# Pro_Micro.net
KiCad netlist of a schematic drawn in EAGLE
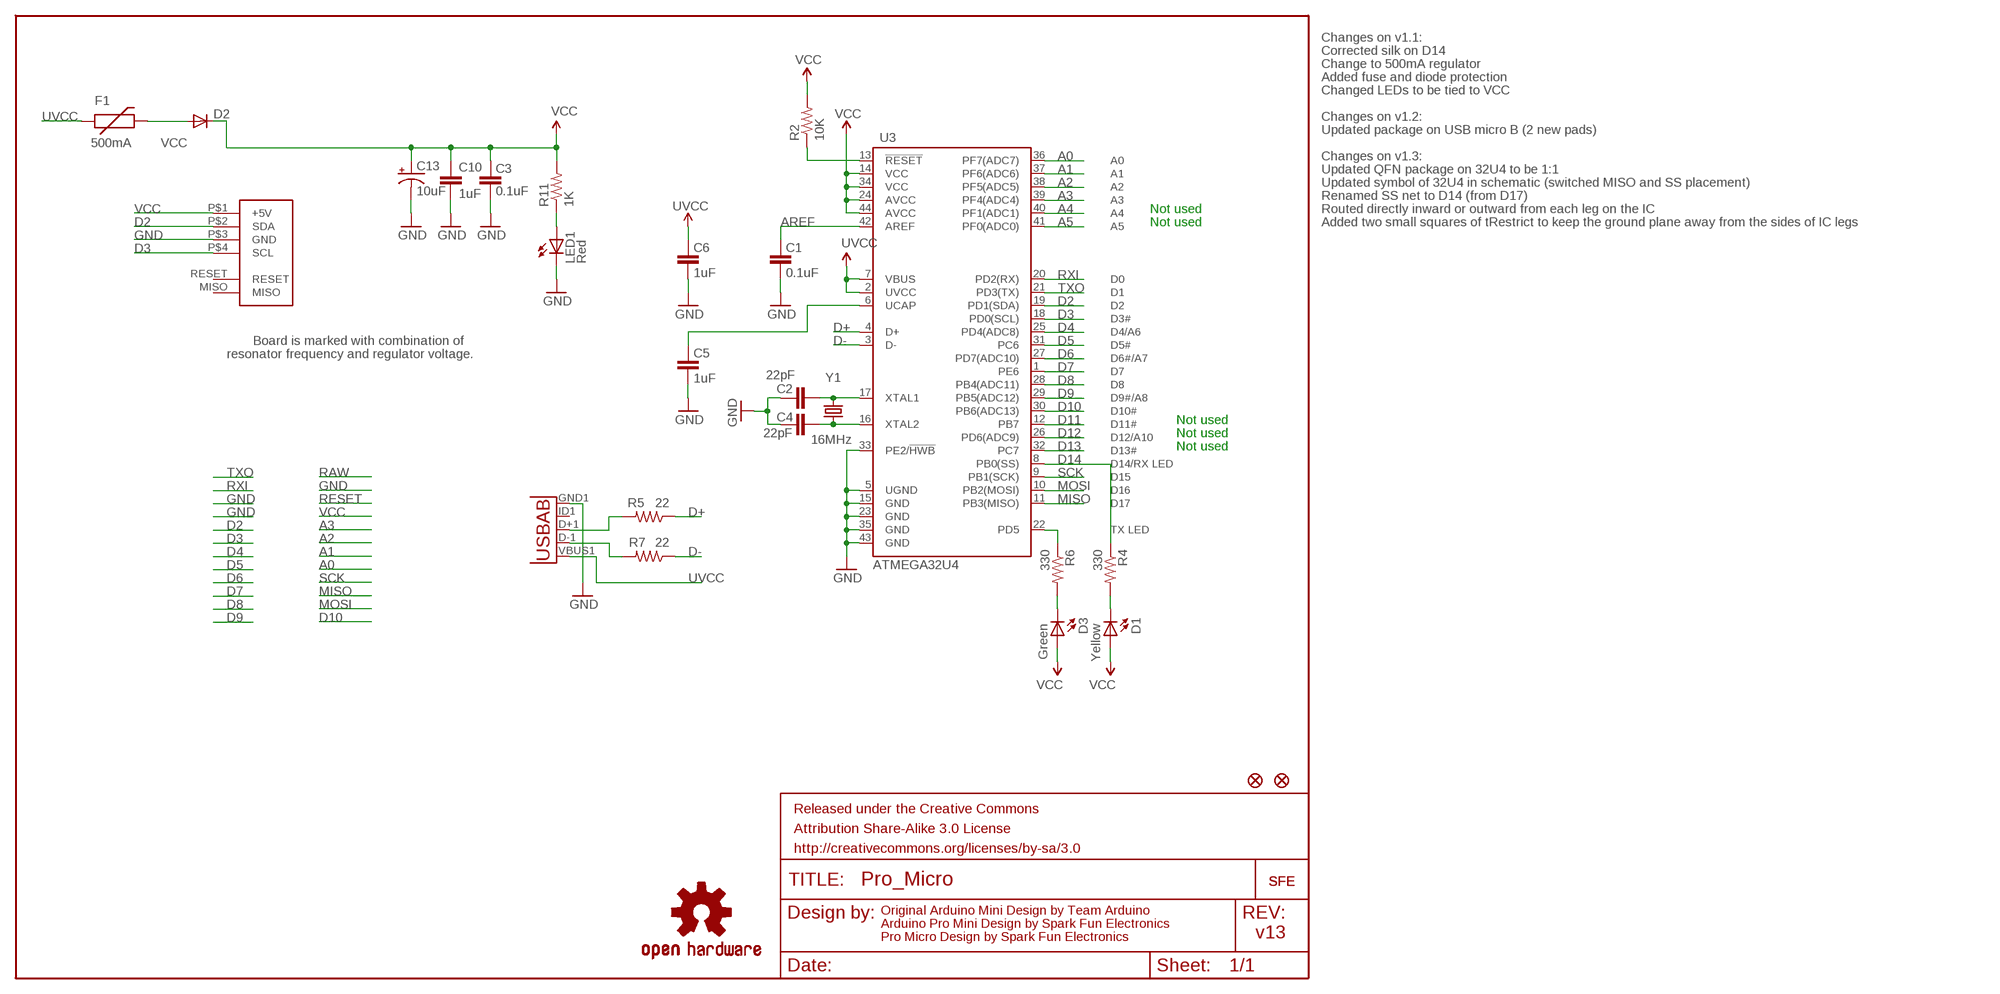
[diagram p0: schematic, sheet 1]

(export (version "E")
  (design (tool "Eeschema 10.0.6"))
  (components
    (comp (ref "C1")
      (value "0.1uF")
      (footprint "eagle-import:0603-CAP")
      (libsource (lib "eagle-import") (part "CAP0603-CAP"))
    )
    (comp (ref "C2")
      (value "22pF")
      (footprint "eagle-import:0603-CAP")
      (libsource (lib "eagle-import") (part "CAP0603-CAP"))
    )
    (comp (ref "C3")
      (value "0.1uF")
      (footprint "eagle-import:0603-CAP")
      (libsource (lib "eagle-import") (part "CAP0603-CAP"))
    )
    (comp (ref "C4")
      (value "22pF")
      (footprint "eagle-import:0603-CAP")
      (libsource (lib "eagle-import") (part "CAP0603-CAP"))
    )
    (comp (ref "C5")
      (value "1uF")
      (footprint "eagle-import:0603-CAP")
      (libsource (lib "eagle-import") (part "CAP0603-CAP"))
    )
    (comp (ref "C6")
      (value "1uF")
      (footprint "eagle-import:0603-CAP")
      (libsource (lib "eagle-import") (part "CAP0603-CAP"))
    )
    (comp (ref "C10")
      (value "1uF")
      (footprint "eagle-import:0603-CAP")
      (libsource (lib "eagle-import") (part "CAP0603-CAP"))
    )
    (comp (ref "C13")
      (value "10uF")
      (footprint "eagle-import:EIA3216")
      (libsource (lib "eagle-import") (part "CAP_POL1206"))
    )
    (comp (ref "D1")
      (value "Yellow")
      (footprint "eagle-import:LED-0603")
      (libsource (lib "eagle-import") (part "LED0603"))
    )
    (comp (ref "D2")
      (value "DIODESOD")
      (footprint "eagle-import:SOD-323")
      (libsource (lib "eagle-import") (part "DIODESOD"))
    )
    (comp (ref "D3")
      (value "Green")
      (footprint "eagle-import:LED-0603")
      (libsource (lib "eagle-import") (part "LED0603"))
    )
    (comp (ref "F1")
      (value "500mA")
      (footprint "eagle-import:PTC-1206")
      (libsource (lib "eagle-import") (part "PTCSMD"))
    )
    (comp (ref "FRAME1")
      (value "FRAME-LETTER")
      (footprint "eagle-import:CREATIVE_COMMONS")
      (libsource (lib "eagle-import") (part "FRAME-LETTER"))
    )
    (comp (ref "JP1")
      (value "FIDUCIALUFIDUCIAL")
      (footprint "eagle-import:MICRO-FIDUCIAL")
      (libsource (lib "eagle-import") (part "FIDUCIALUFIDUCIAL"))
    )
    (comp (ref "JP2")
      (value "FIDUCIALUFIDUCIAL")
      (footprint "eagle-import:MICRO-FIDUCIAL")
      (libsource (lib "eagle-import") (part "FIDUCIALUFIDUCIAL"))
    )
    (comp (ref "LED1")
      (value "Red")
      (footprint "eagle-import:LED-0603")
      (libsource (lib "eagle-import") (part "LED0603"))
    )
    (comp (ref "R2")
      (value "10K")
      (footprint "eagle-import:0603-RES")
      (libsource (lib "eagle-import") (part "RESISTOR0603-RES"))
    )
    (comp (ref "R4")
      (value "330")
      (footprint "eagle-import:0603-RES")
      (libsource (lib "eagle-import") (part "RESISTOR0603-RES"))
    )
    (comp (ref "R5")
      (value "22")
      (footprint "eagle-import:0603-RES")
      (libsource (lib "eagle-import") (part "RESISTOR0603-RES"))
    )
    (comp (ref "R6")
      (value "330")
      (footprint "eagle-import:0603-RES")
      (libsource (lib "eagle-import") (part "RESISTOR0603-RES"))
    )
    (comp (ref "R7")
      (value "22")
      (footprint "eagle-import:0603-RES")
      (libsource (lib "eagle-import") (part "RESISTOR0603-RES"))
    )
    (comp (ref "R11")
      (value "1K")
      (footprint "eagle-import:0603-RES")
      (libsource (lib "eagle-import") (part "RESISTOR0603-RES"))
    )
    (comp (ref "U$1")
      (value "LOGO-SFESK")
      (footprint "eagle-import:SFE-LOGO-FLAME")
      (libsource (lib "eagle-import") (part "LOGO-SFESK"))
    )
    (comp (ref "U$2")
      (value "FOOTPRINT")
      (footprint "eagle-import:FOOTPRINT")
      (libsource (lib "eagle-import") (part "FOOTPRINT"))
    )
    (comp (ref "U$3")
      (value "OSHW-LOGOS")
      (footprint "eagle-import:OSHW-LOGO-S")
      (libsource (lib "eagle-import") (part "OSHW-LOGOS"))
    )
    (comp (ref "U$11")
      (value "LOGO-SFENEW")
      (footprint "eagle-import:SFE-NEW-WEBLOGO")
      (libsource (lib "eagle-import") (part "LOGO-SFENEW"))
    )
    (comp (ref "U3")
      (value "ATMEGA32U4")
      (footprint "eagle-import:QFN-44-NOPAD_1_1-OUTFAKES")
      (libsource (lib "eagle-import") (part "ATMEGA32U4OUTFAKES"))
    )
    (comp (ref "X1")
      (value "USB-ABIN&OUT")
      (footprint "eagle-import:USB-AB-MICRO-SMD-V03-IN&OUT")
      (libsource (lib "eagle-import") (part "USB-ABIN&OUT"))
    )
    (comp (ref "Y1")
      (value "16MHz")
      (footprint "eagle-import:CRYSTAL-SMD-5X3")
      (libsource (lib "eagle-import") (part "CRYSTAL5X3"))
    )
  )
  (nets
    (net (code "1") (name "/A0") (class "Default")
      (node (ref "U3") (pin "36") (pinfunction "PF7(ADC7)_36") (pintype "bidirectional"))
    )
    (net (code "2") (name "/A1") (class "Default")
      (node (ref "U3") (pin "37") (pinfunction "PF6(ADC6)_37") (pintype "bidirectional"))
    )
    (net (code "3") (name "/A2") (class "Default")
      (node (ref "U3") (pin "38") (pinfunction "PF5(ADC5)_38") (pintype "bidirectional"))
    )
    (net (code "4") (name "/A3") (class "Default")
      (node (ref "U3") (pin "39") (pinfunction "PF4(ADC4)_39") (pintype "bidirectional"))
    )
    (net (code "5") (name "/A4") (class "Default")
      (node (ref "U3") (pin "40") (pinfunction "PF1(ADC1)_40") (pintype "bidirectional"))
    )
    (net (code "6") (name "/A5") (class "Default")
      (node (ref "U3") (pin "41") (pinfunction "PF0(ADC0)_41") (pintype "bidirectional"))
    )
    (net (code "7") (name "/AREF") (class "Default")
      (node (ref "C1") (pin "2") (pinfunction "2_2") (pintype "passive"))
      (node (ref "U3") (pin "42") (pinfunction "AREF_42") (pintype "bidirectional"))
    )
    (net (code "8") (name "/D+") (class "Default")
      (node (ref "R5") (pin "1") (pinfunction "1_1") (pintype "passive"))
      (node (ref "U3") (pin "4") (pinfunction "D+_4") (pintype "bidirectional"))
    )
    (net (code "9") (name "/D-") (class "Default")
      (node (ref "R7") (pin "1") (pinfunction "1_1") (pintype "passive"))
      (node (ref "U3") (pin "3") (pinfunction "D-_3") (pintype "bidirectional"))
    )
    (net (code "10") (name "/D2") (class "Default")
      (node (ref "U$2") (pin "P$2") (pinfunction "SDA_P$2") (pintype "bidirectional"))
      (node (ref "U3") (pin "19") (pinfunction "PD1(SDA)_19") (pintype "bidirectional"))
    )
    (net (code "11") (name "/D3") (class "Default")
      (node (ref "U$2") (pin "P$4") (pinfunction "SCL_P$4") (pintype "bidirectional"))
      (node (ref "U3") (pin "18") (pinfunction "PD0(SCL)_18") (pintype "bidirectional"))
    )
    (net (code "12") (name "/D4") (class "Default")
      (node (ref "U3") (pin "25") (pinfunction "PD4(ADC8)_25") (pintype "bidirectional"))
    )
    (net (code "13") (name "/D5") (class "Default")
      (node (ref "U3") (pin "31") (pinfunction "PC6_31") (pintype "bidirectional"))
    )
    (net (code "14") (name "/D6") (class "Default")
      (node (ref "U3") (pin "27") (pinfunction "PD7(ADC10)_27") (pintype "bidirectional"))
    )
    (net (code "15") (name "/D7") (class "Default")
      (node (ref "U3") (pin "1") (pinfunction "PE6_1") (pintype "bidirectional"))
    )
    (net (code "16") (name "/D8") (class "Default")
      (node (ref "U3") (pin "28") (pinfunction "PB4(ADC11)_28") (pintype "bidirectional"))
    )
    (net (code "17") (name "/D9") (class "Default")
      (node (ref "U3") (pin "29") (pinfunction "PB5(ADC12)_29") (pintype "bidirectional"))
    )
    (net (code "18") (name "/D10") (class "Default")
      (node (ref "U3") (pin "30") (pinfunction "PB6(ADC13)_30") (pintype "bidirectional"))
    )
    (net (code "19") (name "/D11") (class "Default")
      (node (ref "U3") (pin "12") (pinfunction "PB7_12") (pintype "bidirectional"))
    )
    (net (code "20") (name "/D12") (class "Default")
      (node (ref "U3") (pin "26") (pinfunction "PD6(ADC9)_26") (pintype "bidirectional"))
    )
    (net (code "21") (name "/D13") (class "Default")
      (node (ref "U3") (pin "32") (pinfunction "PC7_32") (pintype "bidirectional"))
    )
    (net (code "22") (name "/D14") (class "Default")
      (node (ref "R4") (pin "1") (pinfunction "1_1") (pintype "passive"))
      (node (ref "U3") (pin "8") (pinfunction "PB0(SS)_8") (pintype "bidirectional"))
    )
    (net (code "23") (name "/MISO") (class "Default")
      (node (ref "U3") (pin "11") (pinfunction "PB3(MISO)_11") (pintype "bidirectional"))
    )
    (net (code "24") (name "/MOSI") (class "Default")
      (node (ref "U3") (pin "10") (pinfunction "PB2(MOSI)_10") (pintype "bidirectional"))
    )
    (net (code "26") (name "/RESET") (class "Default")
      (node (ref "R2") (pin "1") (pinfunction "1_1") (pintype "passive"))
      (node (ref "U3") (pin "13") (pinfunction "~{RESET}_13") (pintype "bidirectional"))
    )
    (net (code "27") (name "/RXI") (class "Default")
      (node (ref "U3") (pin "20") (pinfunction "PD2(RX)_20") (pintype "bidirectional"))
    )
    (net (code "28") (name "/SCK") (class "Default")
      (node (ref "U3") (pin "9") (pinfunction "PB1(SCK)_9") (pintype "bidirectional"))
    )
    (net (code "29") (name "/TXO") (class "Default")
      (node (ref "U3") (pin "21") (pinfunction "PD3(TX)_21") (pintype "bidirectional"))
    )
    (net (code "30") (name "GND") (class "Default")
      (node (ref "C1") (pin "1") (pinfunction "1_1") (pintype "passive"))
      (node (ref "C10") (pin "2") (pinfunction "2_2") (pintype "passive"))
      (node (ref "C13") (pin "C") (pinfunction "-_C") (pintype "passive"))
      (node (ref "C2") (pin "2") (pinfunction "2_2") (pintype "passive"))
      (node (ref "C3") (pin "1") (pinfunction "1_1") (pintype "passive"))
      (node (ref "C4") (pin "2") (pinfunction "2_2") (pintype "passive"))
      (node (ref "C5") (pin "1") (pinfunction "1_1") (pintype "passive"))
      (node (ref "C6") (pin "1") (pinfunction "1_1") (pintype "passive"))
      (node (ref "LED1") (pin "C") (pinfunction "C_C") (pintype "passive"))
      (node (ref "U$2") (pin "P$3") (pinfunction "GND_P$3") (pintype "power_in"))
      (node (ref "U3") (pin "15") (pinfunction "GND_15") (pintype "bidirectional"))
      (node (ref "U3") (pin "23") (pinfunction "GND_23") (pintype "bidirectional"))
      (node (ref "U3") (pin "33") (pinfunction "PE2/~{HWB}_33") (pintype "bidirectional"))
      (node (ref "U3") (pin "35") (pinfunction "GND_35") (pintype "bidirectional"))
      (node (ref "U3") (pin "43") (pinfunction "GND_43") (pintype "bidirectional"))
      (node (ref "U3") (pin "5") (pinfunction "UGND_5") (pintype "bidirectional"))
      (node (ref "X1") (pin "GND1") (pinfunction "GND_GND1") (pintype "bidirectional"))
    )
    (net (code "31") (name "Net-(D1-PadC)") (class "Default")
      (node (ref "D1") (pin "C") (pinfunction "C_C") (pintype "passive"))
      (node (ref "R4") (pin "2") (pinfunction "2_2") (pintype "passive"))
    )
    (net (code "32") (name "Net-(D2-A)") (class "Default")
      (node (ref "D2") (pin "2") (pinfunction "A_2") (pintype "passive"))
      (node (ref "F1") (pin "2") (pinfunction "2_2") (pintype "bidirectional"))
    )
    (net (code "33") (name "Net-(D3-PadC)") (class "Default")
      (node (ref "D3") (pin "C") (pinfunction "C_C") (pintype "passive"))
      (node (ref "R6") (pin "2") (pinfunction "2_2") (pintype "passive"))
    )
    (net (code "34") (name "Net-(LED1-PadA)") (class "Default")
      (node (ref "LED1") (pin "A") (pinfunction "A_A") (pintype "passive"))
      (node (ref "R11") (pin "1") (pinfunction "1_1") (pintype "passive"))
    )
    (net (code "35") (name "Net-(U3-PD5)") (class "Default")
      (node (ref "R6") (pin "1") (pinfunction "1_1") (pintype "passive"))
      (node (ref "U3") (pin "22") (pinfunction "PD5_22") (pintype "bidirectional"))
    )
    (net (code "36") (name "Net-(U3-UCAP)") (class "Default")
      (node (ref "C5") (pin "2") (pinfunction "2_2") (pintype "passive"))
      (node (ref "U3") (pin "6") (pinfunction "UCAP_6") (pintype "bidirectional"))
    )
    (net (code "37") (name "Net-(U3-XTAL1)") (class "Default")
      (node (ref "C2") (pin "1") (pinfunction "1_1") (pintype "passive"))
      (node (ref "U3") (pin "17") (pinfunction "XTAL1_17") (pintype "bidirectional"))
      (node (ref "Y1") (pin "3") (pinfunction "2_3") (pintype "passive"))
    )
    (net (code "38") (name "Net-(U3-XTAL2)") (class "Default")
      (node (ref "C4") (pin "1") (pinfunction "1_1") (pintype "passive"))
      (node (ref "U3") (pin "16") (pinfunction "XTAL2_16") (pintype "bidirectional"))
      (node (ref "Y1") (pin "1") (pinfunction "1_1") (pintype "passive"))
    )
    (net (code "39") (name "Net-(X1-D+)") (class "Default")
      (node (ref "R5") (pin "2") (pinfunction "2_2") (pintype "passive"))
      (node (ref "X1") (pin "D+1") (pinfunction "D+_D+1") (pintype "bidirectional"))
    )
    (net (code "40") (name "Net-(X1-D-)") (class "Default")
      (node (ref "R7") (pin "2") (pinfunction "2_2") (pintype "passive"))
      (node (ref "X1") (pin "D-1") (pinfunction "D-_D-1") (pintype "bidirectional"))
    )
    (net (code "41") (name "UVCC") (class "Default")
      (node (ref "C6") (pin "2") (pinfunction "2_2") (pintype "passive"))
      (node (ref "F1") (pin "1") (pinfunction "1_1") (pintype "bidirectional"))
      (node (ref "U3") (pin "2") (pinfunction "UVCC_2") (pintype "bidirectional"))
      (node (ref "U3") (pin "7") (pinfunction "VBUS_7") (pintype "bidirectional"))
      (node (ref "X1") (pin "VBUS1") (pinfunction "VBUS_VBUS1") (pintype "bidirectional"))
    )
    (net (code "42") (name "VCC") (class "Default")
      (node (ref "C10") (pin "1") (pinfunction "1_1") (pintype "passive"))
      (node (ref "C13") (pin "A") (pinfunction "+_A") (pintype "passive"))
      (node (ref "C3") (pin "2") (pinfunction "2_2") (pintype "passive"))
      (node (ref "D1") (pin "A") (pinfunction "A_A") (pintype "passive"))
      (node (ref "D2") (pin "1") (pinfunction "C_1") (pintype "passive"))
      (node (ref "D3") (pin "A") (pinfunction "A_A") (pintype "passive"))
      (node (ref "R11") (pin "2") (pinfunction "2_2") (pintype "passive"))
      (node (ref "R2") (pin "2") (pinfunction "2_2") (pintype "passive"))
      (node (ref "U$2") (pin "P$1") (pinfunction "+5V_P$1") (pintype "power_in"))
      (node (ref "U3") (pin "14") (pinfunction "VCC_14") (pintype "bidirectional"))
      (node (ref "U3") (pin "24") (pinfunction "AVCC_24") (pintype "bidirectional"))
      (node (ref "U3") (pin "34") (pinfunction "VCC_34") (pintype "bidirectional"))
      (node (ref "U3") (pin "44") (pinfunction "AVCC_44") (pintype "bidirectional"))
    )
    (net (code "43") (name "unconnected-(U$2-PadMISO)") (class "Default")
      (node (ref "U$2") (pin "MISO") (pinfunction "MISO_MISO") (pintype "bidirectional"))
    )
    (net (code "44") (name "unconnected-(U$2-PadRESET)") (class "Default")
      (node (ref "U$2") (pin "RESET") (pinfunction "RESET_RESET") (pintype "bidirectional"))
    )
    (net (code "45") (name "unconnected-(X1-USBID-PadID1)") (class "Default")
      (node (ref "X1") (pin "ID1") (pinfunction "USBID_ID1") (pintype "bidirectional"))
    )
  )
)
